# pic24rgbrnd01-r2b.net
KiCad netlist of a schematic drawn in EAGLE
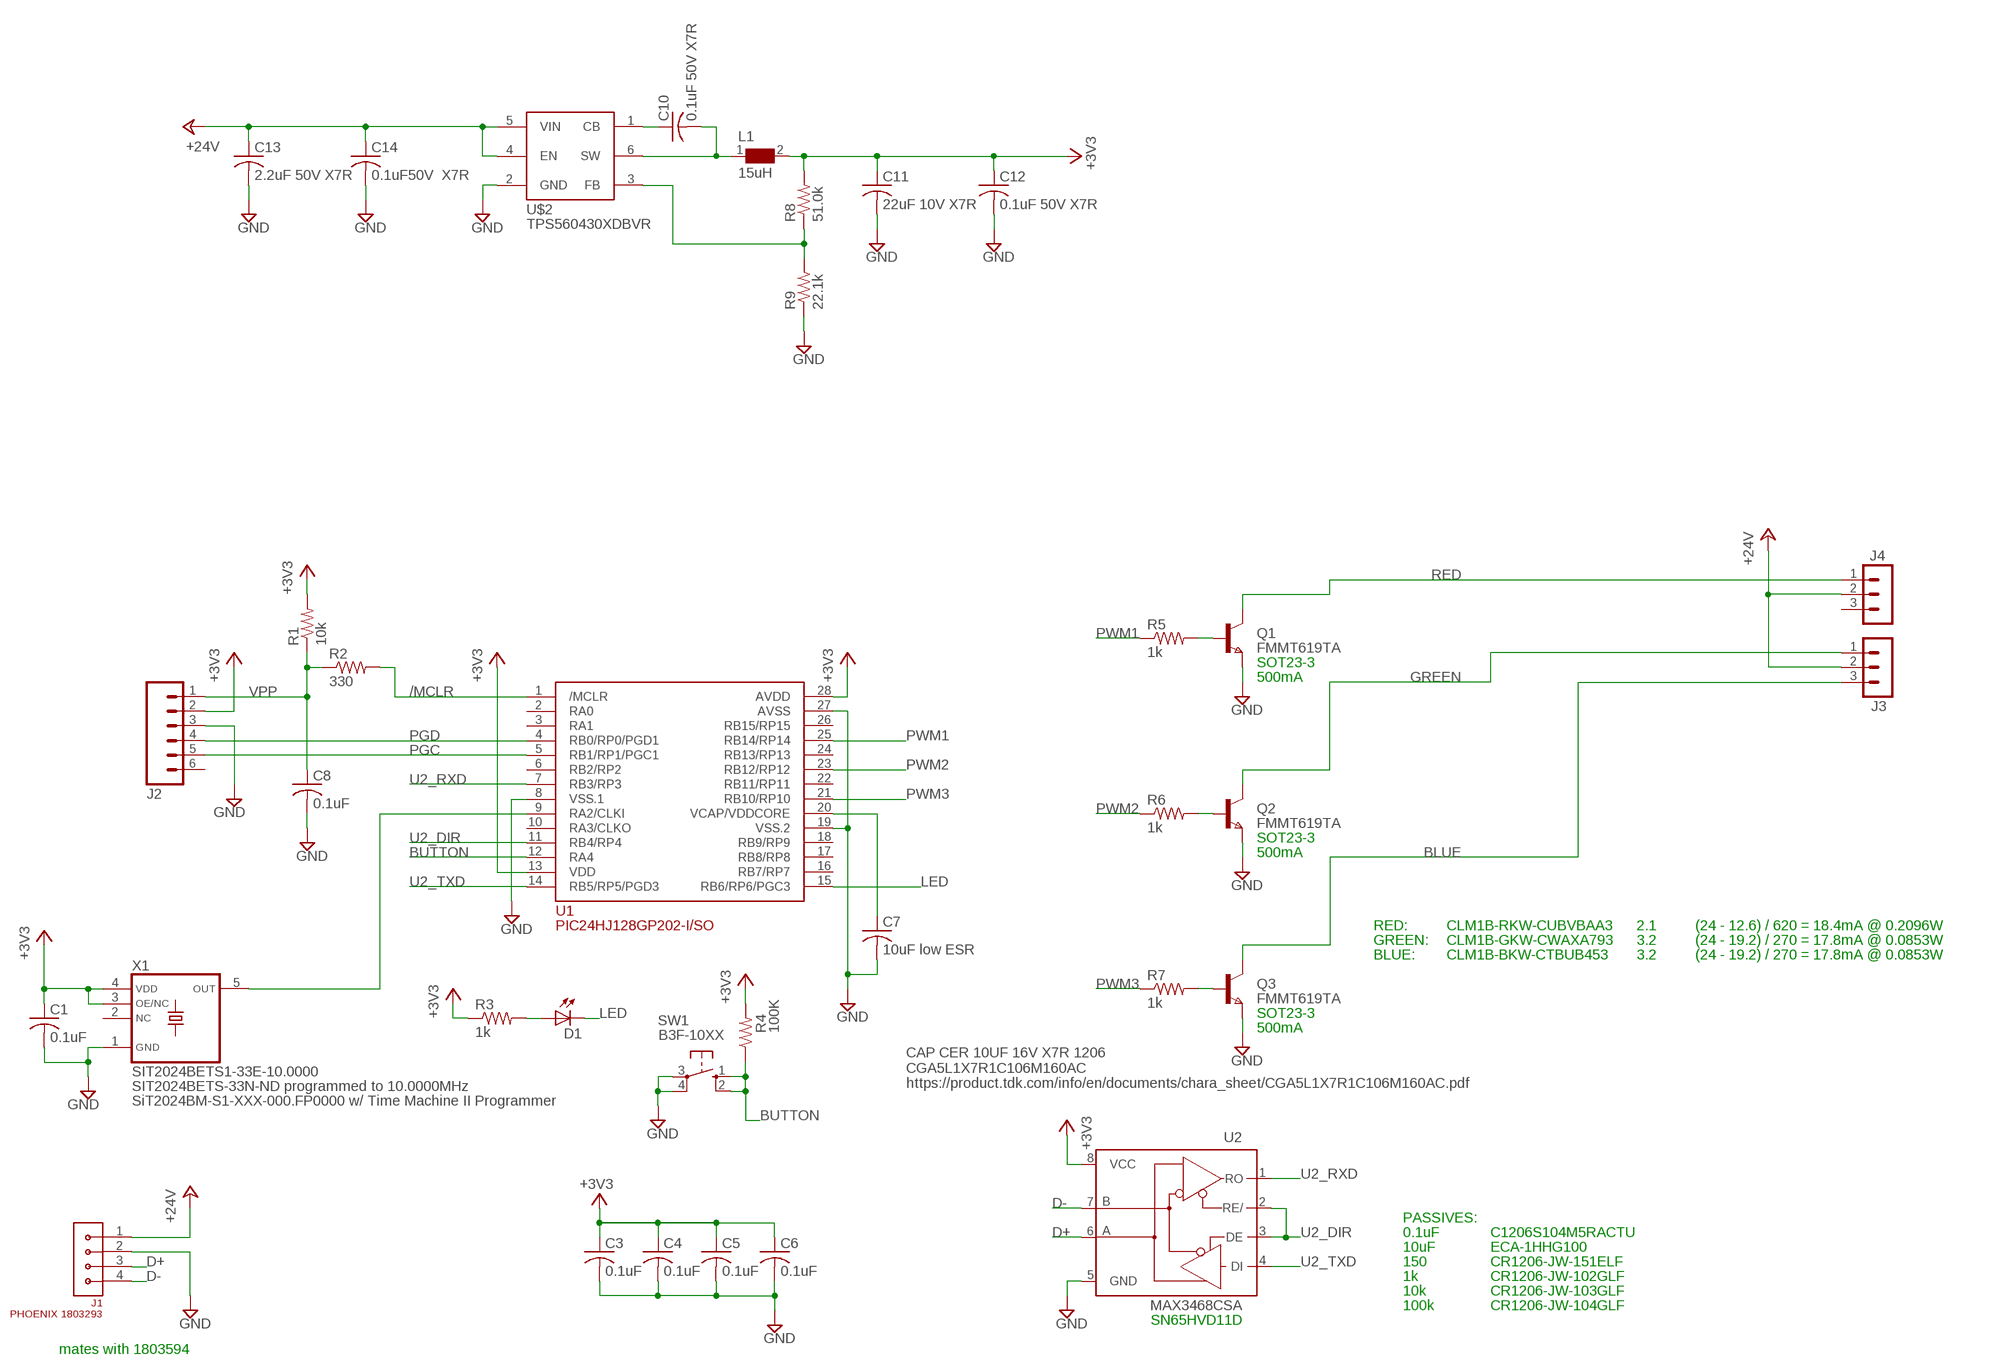
[diagram p0: schematic, sheet 1]

(export (version "E")
  (design (tool "Eeschema 10.0.6"))
  (components
    (comp (ref "C1")
      (value "0.1uF")
      (footprint "eagle-import:C0805")
      (libsource (lib "eagle-import") (part "C-USC0805"))
    )
    (comp (ref "C3")
      (value "0.1uF")
      (footprint "eagle-import:C0805")
      (libsource (lib "eagle-import") (part "C-USC0805"))
    )
    (comp (ref "C4")
      (value "0.1uF")
      (footprint "eagle-import:C0805")
      (libsource (lib "eagle-import") (part "C-USC0805"))
    )
    (comp (ref "C5")
      (value "0.1uF")
      (footprint "eagle-import:C0805")
      (libsource (lib "eagle-import") (part "C-USC0805"))
    )
    (comp (ref "C6")
      (value "0.1uF")
      (footprint "eagle-import:C0805")
      (libsource (lib "eagle-import") (part "C-USC0805"))
    )
    (comp (ref "C7")
      (value "10uF low ESR")
      (footprint "eagle-import:C1206")
      (libsource (lib "eagle-import") (part "resistor_C-USC1206"))
    )
    (comp (ref "C8")
      (value "0.1uF")
      (footprint "eagle-import:C0805")
      (libsource (lib "eagle-import") (part "C-USC0805"))
    )
    (comp (ref "C10")
      (value "0.1uF 50V X7R")
      (footprint "eagle-import:C0805")
      (libsource (lib "eagle-import") (part "C-USC0805"))
    )
    (comp (ref "C11")
      (value "22uF 10V X7R")
      (footprint "eagle-import:C1206K")
      (fields (field (name "MFR") "KEMET") (field (name "MFR_PART_NO") "C1206C226K8RAC7800"))
      (libsource (lib "eagle-import") (part "C-USC1206K"))
    )
    (comp (ref "C12")
      (value "0.1uF 50V X7R")
      (footprint "eagle-import:C0805")
      (libsource (lib "eagle-import") (part "C-USC0805"))
    )
    (comp (ref "C13")
      (value "2.2uF 50V X7R")
      (footprint "eagle-import:C1210K")
      (fields (field (name "MFR") "KEMET") (field (name "MFR_PART_NO") "C1210C106K5RACTU"))
      (libsource (lib "eagle-import") (part "C-USC1210K"))
    )
    (comp (ref "C14")
      (value "0.1uF50V X7R")
      (footprint "eagle-import:C0805")
      (libsource (lib "eagle-import") (part "C-USC0805"))
    )
    (comp (ref "D1")
      (value "LED3MM")
      (footprint "eagle-import:LED3MM")
      (libsource (lib "eagle-import") (part "LED3MM"))
    )
    (comp (ref "J1")
      (value "PHOENIX 1803293")
      (footprint "eagle-import:CON-PHOENIX-1803293-3.81-1X4")
      (libsource (lib "eagle-import") (part "CON-3.81MM-1X4-PHOENIX-1803293"))
    )
    (comp (ref "J2")
      (value "M06SIP")
      (footprint "eagle-import:1X06")
      (libsource (lib "eagle-import") (part "M06SIP"))
    )
    (comp (ref "J3")
      (value "MA03-1")
      (footprint "eagle-import:MA03-1")
      (libsource (lib "eagle-import") (part "MA03-1"))
    )
    (comp (ref "J4")
      (value "MA03-1")
      (footprint "eagle-import:MA03-1")
      (libsource (lib "eagle-import") (part "MA03-1"))
    )
    (comp (ref "L1")
      (value "15uH")
      (footprint "eagle-import:WE-SPC_48XX")
      (fields (field (name "MPN") "74408943150"))
      (libsource (lib "eagle-import") (part "WE-SPC_48XX_4838/4828/4818-74408943150"))
    )
    (comp (ref "Q1")
      (value "FMMT619TA")
      (footprint "eagle-import:SOT-23")
      (fields (field (name "MPN") "DSS20201L-7"))
      (libsource (lib "eagle-import") (part "NPNSOT23"))
    )
    (comp (ref "Q2")
      (value "FMMT619TA")
      (footprint "eagle-import:SOT-23")
      (fields (field (name "MPN") "DSS20201L-7"))
      (libsource (lib "eagle-import") (part "NPNSOT23"))
    )
    (comp (ref "Q3")
      (value "FMMT619TA")
      (footprint "eagle-import:SOT-23")
      (fields (field (name "MPN") "DSS20201L-7"))
      (libsource (lib "eagle-import") (part "NPNSOT23"))
    )
    (comp (ref "R1")
      (value "10k")
      (footprint "eagle-import:R0805")
      (libsource (lib "eagle-import") (part "R-US_R0805"))
    )
    (comp (ref "R2")
      (value "330")
      (footprint "eagle-import:R0805")
      (libsource (lib "eagle-import") (part "R-US_R0805"))
    )
    (comp (ref "R3")
      (value "1k")
      (footprint "eagle-import:R0805")
      (libsource (lib "eagle-import") (part "R-US_R0805"))
    )
    (comp (ref "R4")
      (value "100K")
      (footprint "eagle-import:R0805")
      (libsource (lib "eagle-import") (part "R-US_R0805"))
    )
    (comp (ref "R5")
      (value "1k")
      (footprint "eagle-import:R0805")
      (libsource (lib "eagle-import") (part "R-US_R0805"))
    )
    (comp (ref "R6")
      (value "1k")
      (footprint "eagle-import:R0805")
      (libsource (lib "eagle-import") (part "R-US_R0805"))
    )
    (comp (ref "R7")
      (value "1k")
      (footprint "eagle-import:R0805")
      (libsource (lib "eagle-import") (part "R-US_R0805"))
    )
    (comp (ref "R8")
      (value "51.0k")
      (footprint "eagle-import:R0805")
      (libsource (lib "eagle-import") (part "R-US_R0805"))
    )
    (comp (ref "R9")
      (value "22.1k")
      (footprint "eagle-import:R0805")
      (libsource (lib "eagle-import") (part "R-US_R0805"))
    )
    (comp (ref "SW1")
      (value "B3F-10XX")
      (footprint "eagle-import:B3F-10XX")
      (libsource (lib "eagle-import") (part "10-XX"))
    )
    (comp (ref "U$2")
      (value "TPS560430XDBVR")
      (footprint "eagle-import:SOT23-6")
      (libsource (lib "eagle-import") (part "TPS560430XDBVR"))
    )
    (comp (ref "U1")
      (value "PIC24HJ128GP202-I/SO")
      (footprint "eagle-import:SO28W")
      (libsource (lib "eagle-import") (part "PIC24HJ128GP202-I/SO"))
    )
    (comp (ref "U2")
      (value "MAX3468CSA")
      (footprint "eagle-import:SO08")
      (fields (field (name "MPN") "MAX3468CSA+"))
      (libsource (lib "eagle-import") (part "MAX34SA68C"))
    )
    (comp (ref "X1")
      (value "SIT2024BETS1-33E-10.0000")
      (footprint "eagle-import:SOT23-5")
      (libsource (lib "eagle-import") (part "SIT2024BETS1-33E-10.0000"))
    )
  )
  (nets
    (net (code "1") (name "+3V3") (class "Default")
      (node (ref "C1") (pin "1") (pinfunction "1_1") (pintype "passive"))
      (node (ref "C11") (pin "1") (pinfunction "1_1") (pintype "passive"))
      (node (ref "C12") (pin "1") (pinfunction "1_1") (pintype "passive"))
      (node (ref "C3") (pin "1") (pinfunction "1_1") (pintype "passive"))
      (node (ref "C4") (pin "1") (pinfunction "1_1") (pintype "passive"))
      (node (ref "C5") (pin "1") (pinfunction "1_1") (pintype "passive"))
      (node (ref "C6") (pin "1") (pinfunction "1_1") (pintype "passive"))
      (node (ref "J2") (pin "2") (pinfunction "2_2") (pintype "passive"))
      (node (ref "L1") (pin "2") (pinfunction "2_2") (pintype "passive"))
      (node (ref "R1") (pin "2") (pinfunction "2_2") (pintype "passive"))
      (node (ref "R3") (pin "1") (pinfunction "1_1") (pintype "passive"))
      (node (ref "R4") (pin "2") (pinfunction "2_2") (pintype "passive"))
      (node (ref "R8") (pin "2") (pinfunction "2_2") (pintype "passive"))
      (node (ref "U1") (pin "13") (pinfunction "VDD_13") (pintype "bidirectional"))
      (node (ref "U1") (pin "28") (pinfunction "AVDD_28") (pintype "bidirectional"))
      (node (ref "U2") (pin "8") (pinfunction "VCC_8") (pintype "power_in"))
      (node (ref "X1") (pin "3") (pinfunction "OE/NC_3") (pintype "bidirectional"))
      (node (ref "X1") (pin "4") (pinfunction "VDD_4") (pintype "bidirectional"))
    )
    (net (code "2") (name "+24V") (class "Default")
      (node (ref "C13") (pin "1") (pinfunction "1_1") (pintype "passive"))
      (node (ref "C14") (pin "1") (pinfunction "1_1") (pintype "passive"))
      (node (ref "J1") (pin "1") (pinfunction "1_1") (pintype "bidirectional"))
      (node (ref "J3") (pin "2") (pinfunction "2_2") (pintype "passive"))
      (node (ref "J4") (pin "2") (pinfunction "2_2") (pintype "passive"))
      (node (ref "U$2") (pin "4") (pinfunction "EN_4") (pintype "bidirectional"))
      (node (ref "U$2") (pin "5") (pinfunction "VIN_5") (pintype "bidirectional"))
    )
    (net (code "3") (name "/BLUE") (class "Default")
      (node (ref "J3") (pin "3") (pinfunction "3_3") (pintype "passive"))
      (node (ref "Q3") (pin "1") (pinfunction "C_1") (pintype "passive"))
    )
    (net (code "4") (name "/BUTTON") (class "Default")
      (node (ref "R4") (pin "1") (pinfunction "1_1") (pintype "passive"))
      (node (ref "SW1") (pin "1") (pinfunction "S_1") (pintype "passive"))
      (node (ref "SW1") (pin "2") (pinfunction "S1_2") (pintype "passive"))
      (node (ref "U1") (pin "12") (pinfunction "RA4_12") (pintype "bidirectional"))
    )
    (net (code "5") (name "/D+") (class "Default")
      (node (ref "J1") (pin "3") (pinfunction "3_3") (pintype "bidirectional"))
      (node (ref "U2") (pin "6") (pinfunction "A_6") (pintype "passive"))
    )
    (net (code "6") (name "/D-") (class "Default")
      (node (ref "J1") (pin "4") (pinfunction "4_4") (pintype "bidirectional"))
      (node (ref "U2") (pin "7") (pinfunction "B_7") (pintype "passive"))
    )
    (net (code "7") (name "/GREEN") (class "Default")
      (node (ref "J3") (pin "1") (pinfunction "1_1") (pintype "passive"))
      (node (ref "Q2") (pin "1") (pinfunction "C_1") (pintype "passive"))
    )
    (net (code "8") (name "/LED") (class "Default")
      (node (ref "D1") (pin "K") (pinfunction "C_K") (pintype "passive"))
      (node (ref "U1") (pin "15") (pinfunction "RB6/RP6/PGC3_15") (pintype "bidirectional"))
    )
    (net (code "9") (name "/PGC") (class "Default")
      (node (ref "J2") (pin "5") (pinfunction "5_5") (pintype "passive"))
      (node (ref "U1") (pin "5") (pinfunction "RB1/RP1/PGC1_5") (pintype "bidirectional"))
    )
    (net (code "10") (name "/PGD") (class "Default")
      (node (ref "J2") (pin "4") (pinfunction "4_4") (pintype "passive"))
      (node (ref "U1") (pin "4") (pinfunction "RB0/RP0/PGD1_4") (pintype "bidirectional"))
    )
    (net (code "11") (name "/PWM1") (class "Default")
      (node (ref "R5") (pin "1") (pinfunction "1_1") (pintype "passive"))
      (node (ref "U1") (pin "25") (pinfunction "RB14/RP14_25") (pintype "bidirectional"))
    )
    (net (code "12") (name "/PWM2") (class "Default")
      (node (ref "R6") (pin "1") (pinfunction "1_1") (pintype "passive"))
      (node (ref "U1") (pin "23") (pinfunction "RB12/RP12_23") (pintype "bidirectional"))
    )
    (net (code "13") (name "/PWM3") (class "Default")
      (node (ref "R7") (pin "1") (pinfunction "1_1") (pintype "passive"))
      (node (ref "U1") (pin "21") (pinfunction "RB10/RP10_21") (pintype "bidirectional"))
    )
    (net (code "14") (name "/RED") (class "Default")
      (node (ref "J4") (pin "1") (pinfunction "1_1") (pintype "passive"))
      (node (ref "Q1") (pin "1") (pinfunction "C_1") (pintype "passive"))
    )
    (net (code "15") (name "/U2_DIR") (class "Default")
      (node (ref "U1") (pin "11") (pinfunction "RB4/RP4_11") (pintype "bidirectional"))
      (node (ref "U2") (pin "2") (pinfunction "RE/_2") (pintype "input"))
      (node (ref "U2") (pin "3") (pinfunction "DE_3") (pintype "input"))
    )
    (net (code "16") (name "/U2_RXD") (class "Default")
      (node (ref "U1") (pin "7") (pinfunction "RB3/RP3_7") (pintype "bidirectional"))
      (node (ref "U2") (pin "1") (pinfunction "RO_1") (pintype "output"))
    )
    (net (code "17") (name "/U2_TXD") (class "Default")
      (node (ref "U1") (pin "14") (pinfunction "RB5/RP5/PGD3_14") (pintype "bidirectional"))
      (node (ref "U2") (pin "4") (pinfunction "DI_4") (pintype "input"))
    )
    (net (code "18") (name "/VPP") (class "Default")
      (node (ref "C8") (pin "1") (pinfunction "1_1") (pintype "passive"))
      (node (ref "J2") (pin "1") (pinfunction "1_1") (pintype "passive"))
      (node (ref "R1") (pin "1") (pinfunction "1_1") (pintype "passive"))
      (node (ref "R2") (pin "1") (pinfunction "1_1") (pintype "passive"))
    )
    (net (code "19") (name "/{slash}MCLR") (class "Default")
      (node (ref "R2") (pin "2") (pinfunction "2_2") (pintype "passive"))
      (node (ref "U1") (pin "1") (pinfunction "/MCLR_1") (pintype "bidirectional"))
    )
    (net (code "20") (name "GND") (class "Default")
      (node (ref "C1") (pin "2") (pinfunction "2_2") (pintype "passive"))
      (node (ref "C11") (pin "2") (pinfunction "2_2") (pintype "passive"))
      (node (ref "C12") (pin "2") (pinfunction "2_2") (pintype "passive"))
      (node (ref "C13") (pin "2") (pinfunction "2_2") (pintype "passive"))
      (node (ref "C14") (pin "2") (pinfunction "2_2") (pintype "passive"))
      (node (ref "C3") (pin "2") (pinfunction "2_2") (pintype "passive"))
      (node (ref "C4") (pin "2") (pinfunction "2_2") (pintype "passive"))
      (node (ref "C5") (pin "2") (pinfunction "2_2") (pintype "passive"))
      (node (ref "C6") (pin "2") (pinfunction "2_2") (pintype "passive"))
      (node (ref "C7") (pin "2") (pinfunction "2_2") (pintype "passive"))
      (node (ref "C8") (pin "2") (pinfunction "2_2") (pintype "passive"))
      (node (ref "J1") (pin "2") (pinfunction "2_2") (pintype "bidirectional"))
      (node (ref "J2") (pin "3") (pinfunction "3_3") (pintype "passive"))
      (node (ref "Q1") (pin "2") (pinfunction "E_2") (pintype "passive"))
      (node (ref "Q2") (pin "2") (pinfunction "E_2") (pintype "passive"))
      (node (ref "Q3") (pin "2") (pinfunction "E_2") (pintype "passive"))
      (node (ref "R9") (pin "1") (pinfunction "1_1") (pintype "passive"))
      (node (ref "SW1") (pin "3") (pinfunction "P_3") (pintype "passive"))
      (node (ref "SW1") (pin "4") (pinfunction "P1_4") (pintype "passive"))
      (node (ref "U$2") (pin "2") (pinfunction "GND_2") (pintype "bidirectional"))
      (node (ref "U1") (pin "19") (pinfunction "VSS.2_19") (pintype "bidirectional"))
      (node (ref "U1") (pin "27") (pinfunction "AVSS_27") (pintype "bidirectional"))
      (node (ref "U1") (pin "8") (pinfunction "VSS.1_8") (pintype "bidirectional"))
      (node (ref "U2") (pin "5") (pinfunction "GND_5") (pintype "power_in"))
      (node (ref "X1") (pin "1") (pinfunction "GND_1") (pintype "bidirectional"))
    )
    (net (code "21") (name "Net-(D1-PadA)") (class "Default")
      (node (ref "D1") (pin "A") (pinfunction "A_A") (pintype "passive"))
      (node (ref "R3") (pin "2") (pinfunction "2_2") (pintype "passive"))
    )
    (net (code "22") (name "Net-(Q1-B)") (class "Default")
      (node (ref "Q1") (pin "3") (pinfunction "B_3") (pintype "passive"))
      (node (ref "R5") (pin "2") (pinfunction "2_2") (pintype "passive"))
    )
    (net (code "23") (name "Net-(Q2-B)") (class "Default")
      (node (ref "Q2") (pin "3") (pinfunction "B_3") (pintype "passive"))
      (node (ref "R6") (pin "2") (pinfunction "2_2") (pintype "passive"))
    )
    (net (code "24") (name "Net-(Q3-B)") (class "Default")
      (node (ref "Q3") (pin "3") (pinfunction "B_3") (pintype "passive"))
      (node (ref "R7") (pin "2") (pinfunction "2_2") (pintype "passive"))
    )
    (net (code "25") (name "Net-(U$2-CB)") (class "Default")
      (node (ref "C10") (pin "1") (pinfunction "1_1") (pintype "passive"))
      (node (ref "U$2") (pin "1") (pinfunction "CB_1") (pintype "bidirectional"))
    )
    (net (code "26") (name "Net-(U$2-FB)") (class "Default")
      (node (ref "R8") (pin "1") (pinfunction "1_1") (pintype "passive"))
      (node (ref "R9") (pin "2") (pinfunction "2_2") (pintype "passive"))
      (node (ref "U$2") (pin "3") (pinfunction "FB_3") (pintype "bidirectional"))
    )
    (net (code "27") (name "Net-(U$2-SW)") (class "Default")
      (node (ref "C10") (pin "2") (pinfunction "2_2") (pintype "passive"))
      (node (ref "L1") (pin "1") (pinfunction "1_1") (pintype "passive"))
      (node (ref "U$2") (pin "6") (pinfunction "SW_6") (pintype "bidirectional"))
    )
    (net (code "28") (name "Net-(U1-RA2{slash}CLKI)") (class "Default")
      (node (ref "U1") (pin "9") (pinfunction "RA2/CLKI_9") (pintype "bidirectional"))
      (node (ref "X1") (pin "5") (pinfunction "OUT_5") (pintype "bidirectional"))
    )
    (net (code "29") (name "Net-(U1-VCAP{slash}VDDCORE)") (class "Default")
      (node (ref "C7") (pin "1") (pinfunction "1_1") (pintype "passive"))
      (node (ref "U1") (pin "20") (pinfunction "VCAP/VDDCORE_20") (pintype "bidirectional"))
    )
    (net (code "30") (name "unconnected-(J2-Pad6)") (class "Default")
      (node (ref "J2") (pin "6") (pinfunction "6_6") (pintype "passive"))
    )
    (net (code "31") (name "unconnected-(J4-Pad3)") (class "Default")
      (node (ref "J4") (pin "3") (pinfunction "3_3") (pintype "passive"))
    )
    (net (code "32") (name "unconnected-(U1-RA0-Pad2)") (class "Default")
      (node (ref "U1") (pin "2") (pinfunction "RA0_2") (pintype "bidirectional"))
    )
    (net (code "33") (name "unconnected-(U1-RA1-Pad3)") (class "Default")
      (node (ref "U1") (pin "3") (pinfunction "RA1_3") (pintype "bidirectional"))
    )
    (net (code "34") (name "unconnected-(U1-RA3{slash}CLKO-Pad10)") (class "Default")
      (node (ref "U1") (pin "10") (pinfunction "RA3/CLKO_10") (pintype "bidirectional"))
    )
    (net (code "35") (name "unconnected-(U1-RB2{slash}RP2-Pad6)") (class "Default")
      (node (ref "U1") (pin "6") (pinfunction "RB2/RP2_6") (pintype "bidirectional"))
    )
    (net (code "36") (name "unconnected-(U1-RB7{slash}RP7-Pad16)") (class "Default")
      (node (ref "U1") (pin "16") (pinfunction "RB7/RP7_16") (pintype "bidirectional"))
    )
    (net (code "37") (name "unconnected-(U1-RB8{slash}RP8-Pad17)") (class "Default")
      (node (ref "U1") (pin "17") (pinfunction "RB8/RP8_17") (pintype "bidirectional"))
    )
    (net (code "38") (name "unconnected-(U1-RB9{slash}RP9-Pad18)") (class "Default")
      (node (ref "U1") (pin "18") (pinfunction "RB9/RP9_18") (pintype "bidirectional"))
    )
    (net (code "39") (name "unconnected-(U1-RB11{slash}RP11-Pad22)") (class "Default")
      (node (ref "U1") (pin "22") (pinfunction "RB11/RP11_22") (pintype "bidirectional"))
    )
    (net (code "40") (name "unconnected-(U1-RB13{slash}RP13-Pad24)") (class "Default")
      (node (ref "U1") (pin "24") (pinfunction "RB13/RP13_24") (pintype "bidirectional"))
    )
    (net (code "41") (name "unconnected-(U1-RB15{slash}RP15-Pad26)") (class "Default")
      (node (ref "U1") (pin "26") (pinfunction "RB15/RP15_26") (pintype "bidirectional"))
    )
    (net (code "42") (name "unconnected-(X1-NC-Pad2)") (class "Default")
      (node (ref "X1") (pin "2") (pinfunction "NC_2") (pintype "bidirectional"))
    )
  )
)
